# esquematico2.net
KiCad netlist of a schematic drawn in EAGLE
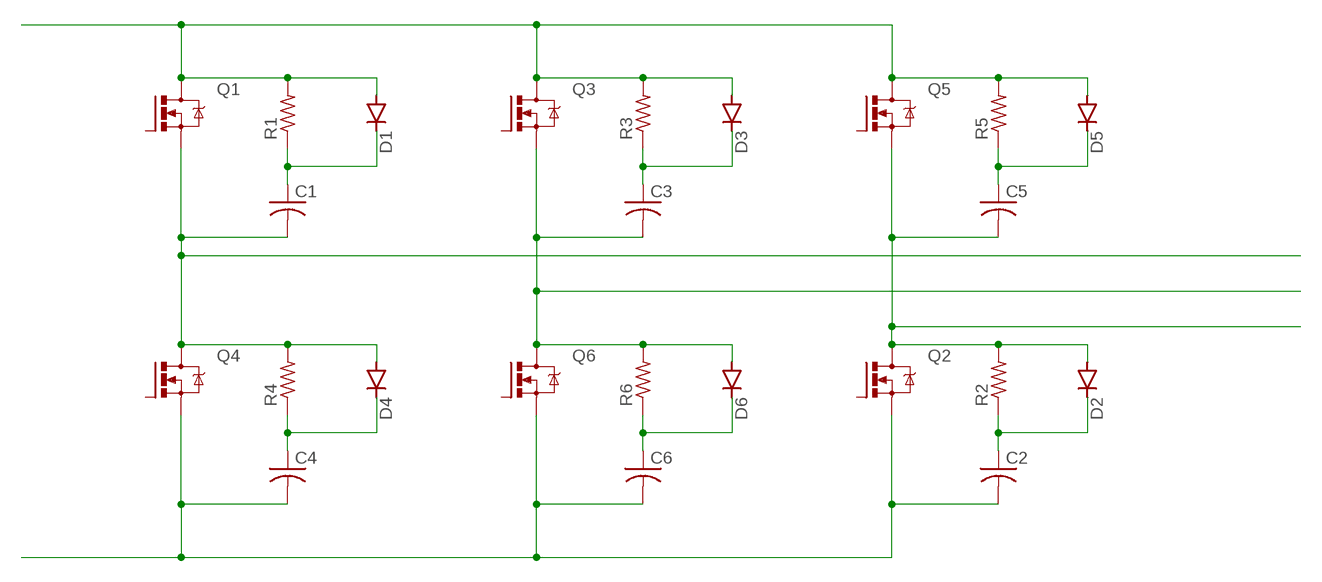
[diagram p0: schematic, sheet 1]

(export (version "E")
  (design (tool "Eeschema 10.0.6"))
  (components
    (comp (ref "C1")
      (value "C-US025-024X044")
      (footprint "eagle-import:C025-024X044")
      (libsource (lib "eagle-import") (part "C-US025-024X044"))
    )
    (comp (ref "C2")
      (value "C-US025-024X044")
      (footprint "eagle-import:C025-024X044")
      (libsource (lib "eagle-import") (part "C-US025-024X044"))
    )
    (comp (ref "C3")
      (value "C-US025-024X044")
      (footprint "eagle-import:C025-024X044")
      (libsource (lib "eagle-import") (part "C-US025-024X044"))
    )
    (comp (ref "C4")
      (value "C-US025-024X044")
      (footprint "eagle-import:C025-024X044")
      (libsource (lib "eagle-import") (part "C-US025-024X044"))
    )
    (comp (ref "C5")
      (value "C-US025-024X044")
      (footprint "eagle-import:C025-024X044")
      (libsource (lib "eagle-import") (part "C-US025-024X044"))
    )
    (comp (ref "C6")
      (value "C-US025-024X044")
      (footprint "eagle-import:C025-024X044")
      (libsource (lib "eagle-import") (part "C-US025-024X044"))
    )
    (comp (ref "D1")
      (value "1N4004")
      (footprint "eagle-import:DO41-10")
      (libsource (lib "eagle-import") (part "1N4004"))
    )
    (comp (ref "D2")
      (value "1N4004")
      (footprint "eagle-import:DO41-10")
      (libsource (lib "eagle-import") (part "1N4004"))
    )
    (comp (ref "D3")
      (value "1N4004")
      (footprint "eagle-import:DO41-10")
      (libsource (lib "eagle-import") (part "1N4004"))
    )
    (comp (ref "D4")
      (value "1N4004")
      (footprint "eagle-import:DO41-10")
      (libsource (lib "eagle-import") (part "1N4004"))
    )
    (comp (ref "D5")
      (value "1N4004")
      (footprint "eagle-import:DO41-10")
      (libsource (lib "eagle-import") (part "1N4004"))
    )
    (comp (ref "D6")
      (value "1N4004")
      (footprint "eagle-import:DO41-10")
      (libsource (lib "eagle-import") (part "1N4004"))
    )
    (comp (ref "Q1")
      (value "IRF540")
      (footprint "eagle-import:TO220BV")
      (libsource (lib "eagle-import") (part "IRF540"))
    )
    (comp (ref "Q2")
      (value "IRF540")
      (footprint "eagle-import:TO220BV")
      (libsource (lib "eagle-import") (part "IRF540"))
    )
    (comp (ref "Q3")
      (value "IRF540")
      (footprint "eagle-import:TO220BV")
      (libsource (lib "eagle-import") (part "IRF540"))
    )
    (comp (ref "Q4")
      (value "IRF540")
      (footprint "eagle-import:TO220BV")
      (libsource (lib "eagle-import") (part "IRF540"))
    )
    (comp (ref "Q5")
      (value "IRF540")
      (footprint "eagle-import:TO220BV")
      (libsource (lib "eagle-import") (part "IRF540"))
    )
    (comp (ref "Q6")
      (value "IRF540")
      (footprint "eagle-import:TO220BV")
      (libsource (lib "eagle-import") (part "IRF540"))
    )
    (comp (ref "R1")
      (value "FLIPFLOP-RES")
      (footprint "eagle-import:0805-THM")
      (libsource (lib "eagle-import") (part "FLIPFLOP-RES"))
    )
    (comp (ref "R2")
      (value "FLIPFLOP-RES")
      (footprint "eagle-import:0805-THM")
      (libsource (lib "eagle-import") (part "FLIPFLOP-RES"))
    )
    (comp (ref "R3")
      (value "FLIPFLOP-RES")
      (footprint "eagle-import:0805-THM")
      (libsource (lib "eagle-import") (part "FLIPFLOP-RES"))
    )
    (comp (ref "R4")
      (value "FLIPFLOP-RES")
      (footprint "eagle-import:0805-THM")
      (libsource (lib "eagle-import") (part "FLIPFLOP-RES"))
    )
    (comp (ref "R5")
      (value "FLIPFLOP-RES")
      (footprint "eagle-import:0805-THM")
      (libsource (lib "eagle-import") (part "FLIPFLOP-RES"))
    )
    (comp (ref "R6")
      (value "FLIPFLOP-RES")
      (footprint "eagle-import:0805-THM")
      (libsource (lib "eagle-import") (part "FLIPFLOP-RES"))
    )
  )
  (nets
    (net (code "1") (name "Net-(C1-Pad1)") (class "Default")
      (node (ref "C1") (pin "1") (pinfunction "1_1") (pintype "passive"))
      (node (ref "D1") (pin "C") (pinfunction "C_C") (pintype "passive"))
      (node (ref "R1") (pin "1") (pinfunction "1_1") (pintype "passive"))
    )
    (net (code "2") (name "Net-(C1-Pad2)") (class "Default")
      (node (ref "C1") (pin "2") (pinfunction "2_2") (pintype "passive"))
      (node (ref "D4") (pin "A") (pinfunction "A_A") (pintype "passive"))
      (node (ref "Q1") (pin "S") (pinfunction "S_S") (pintype "passive"))
      (node (ref "Q4") (pin "D") (pinfunction "D_D") (pintype "passive"))
      (node (ref "R4") (pin "2") (pinfunction "2_2") (pintype "passive"))
    )
    (net (code "3") (name "Net-(C2-Pad1)") (class "Default")
      (node (ref "C2") (pin "1") (pinfunction "1_1") (pintype "passive"))
      (node (ref "D2") (pin "C") (pinfunction "C_C") (pintype "passive"))
      (node (ref "R2") (pin "1") (pinfunction "1_1") (pintype "passive"))
    )
    (net (code "4") (name "Net-(C2-Pad2)") (class "Default")
      (node (ref "C2") (pin "2") (pinfunction "2_2") (pintype "passive"))
      (node (ref "C4") (pin "2") (pinfunction "2_2") (pintype "passive"))
      (node (ref "C6") (pin "2") (pinfunction "2_2") (pintype "passive"))
      (node (ref "Q2") (pin "S") (pinfunction "S_S") (pintype "passive"))
      (node (ref "Q4") (pin "S") (pinfunction "S_S") (pintype "passive"))
      (node (ref "Q6") (pin "S") (pinfunction "S_S") (pintype "passive"))
    )
    (net (code "5") (name "Net-(C3-Pad1)") (class "Default")
      (node (ref "C3") (pin "1") (pinfunction "1_1") (pintype "passive"))
      (node (ref "D3") (pin "C") (pinfunction "C_C") (pintype "passive"))
      (node (ref "R3") (pin "1") (pinfunction "1_1") (pintype "passive"))
    )
    (net (code "6") (name "Net-(C3-Pad2)") (class "Default")
      (node (ref "C3") (pin "2") (pinfunction "2_2") (pintype "passive"))
      (node (ref "D6") (pin "A") (pinfunction "A_A") (pintype "passive"))
      (node (ref "Q3") (pin "S") (pinfunction "S_S") (pintype "passive"))
      (node (ref "Q6") (pin "D") (pinfunction "D_D") (pintype "passive"))
      (node (ref "R6") (pin "2") (pinfunction "2_2") (pintype "passive"))
    )
    (net (code "7") (name "Net-(C4-Pad1)") (class "Default")
      (node (ref "C4") (pin "1") (pinfunction "1_1") (pintype "passive"))
      (node (ref "D4") (pin "C") (pinfunction "C_C") (pintype "passive"))
      (node (ref "R4") (pin "1") (pinfunction "1_1") (pintype "passive"))
    )
    (net (code "8") (name "Net-(C5-Pad1)") (class "Default")
      (node (ref "C5") (pin "1") (pinfunction "1_1") (pintype "passive"))
      (node (ref "D5") (pin "C") (pinfunction "C_C") (pintype "passive"))
      (node (ref "R5") (pin "1") (pinfunction "1_1") (pintype "passive"))
    )
    (net (code "9") (name "Net-(C5-Pad2)") (class "Default")
      (node (ref "C5") (pin "2") (pinfunction "2_2") (pintype "passive"))
      (node (ref "D2") (pin "A") (pinfunction "A_A") (pintype "passive"))
      (node (ref "Q2") (pin "D") (pinfunction "D_D") (pintype "passive"))
      (node (ref "Q5") (pin "S") (pinfunction "S_S") (pintype "passive"))
      (node (ref "R2") (pin "2") (pinfunction "2_2") (pintype "passive"))
    )
    (net (code "10") (name "Net-(C6-Pad1)") (class "Default")
      (node (ref "C6") (pin "1") (pinfunction "1_1") (pintype "passive"))
      (node (ref "D6") (pin "C") (pinfunction "C_C") (pintype "passive"))
      (node (ref "R6") (pin "1") (pinfunction "1_1") (pintype "passive"))
    )
    (net (code "11") (name "Net-(D1-PadA)") (class "Default")
      (node (ref "D1") (pin "A") (pinfunction "A_A") (pintype "passive"))
      (node (ref "D3") (pin "A") (pinfunction "A_A") (pintype "passive"))
      (node (ref "D5") (pin "A") (pinfunction "A_A") (pintype "passive"))
      (node (ref "Q1") (pin "D") (pinfunction "D_D") (pintype "passive"))
      (node (ref "Q3") (pin "D") (pinfunction "D_D") (pintype "passive"))
      (node (ref "Q5") (pin "D") (pinfunction "D_D") (pintype "passive"))
      (node (ref "R1") (pin "2") (pinfunction "2_2") (pintype "passive"))
      (node (ref "R3") (pin "2") (pinfunction "2_2") (pintype "passive"))
      (node (ref "R5") (pin "2") (pinfunction "2_2") (pintype "passive"))
    )
    (net (code "12") (name "unconnected-(Q1-PadG)") (class "Default")
      (node (ref "Q1") (pin "G") (pinfunction "G_G") (pintype "passive"))
    )
    (net (code "13") (name "unconnected-(Q2-PadG)") (class "Default")
      (node (ref "Q2") (pin "G") (pinfunction "G_G") (pintype "passive"))
    )
    (net (code "14") (name "unconnected-(Q3-PadG)") (class "Default")
      (node (ref "Q3") (pin "G") (pinfunction "G_G") (pintype "passive"))
    )
    (net (code "15") (name "unconnected-(Q4-PadG)") (class "Default")
      (node (ref "Q4") (pin "G") (pinfunction "G_G") (pintype "passive"))
    )
    (net (code "16") (name "unconnected-(Q5-PadG)") (class "Default")
      (node (ref "Q5") (pin "G") (pinfunction "G_G") (pintype "passive"))
    )
    (net (code "17") (name "unconnected-(Q6-PadG)") (class "Default")
      (node (ref "Q6") (pin "G") (pinfunction "G_G") (pintype "passive"))
    )
  )
)
